# master.net
KiCad netlist of a schematic drawn in EAGLE
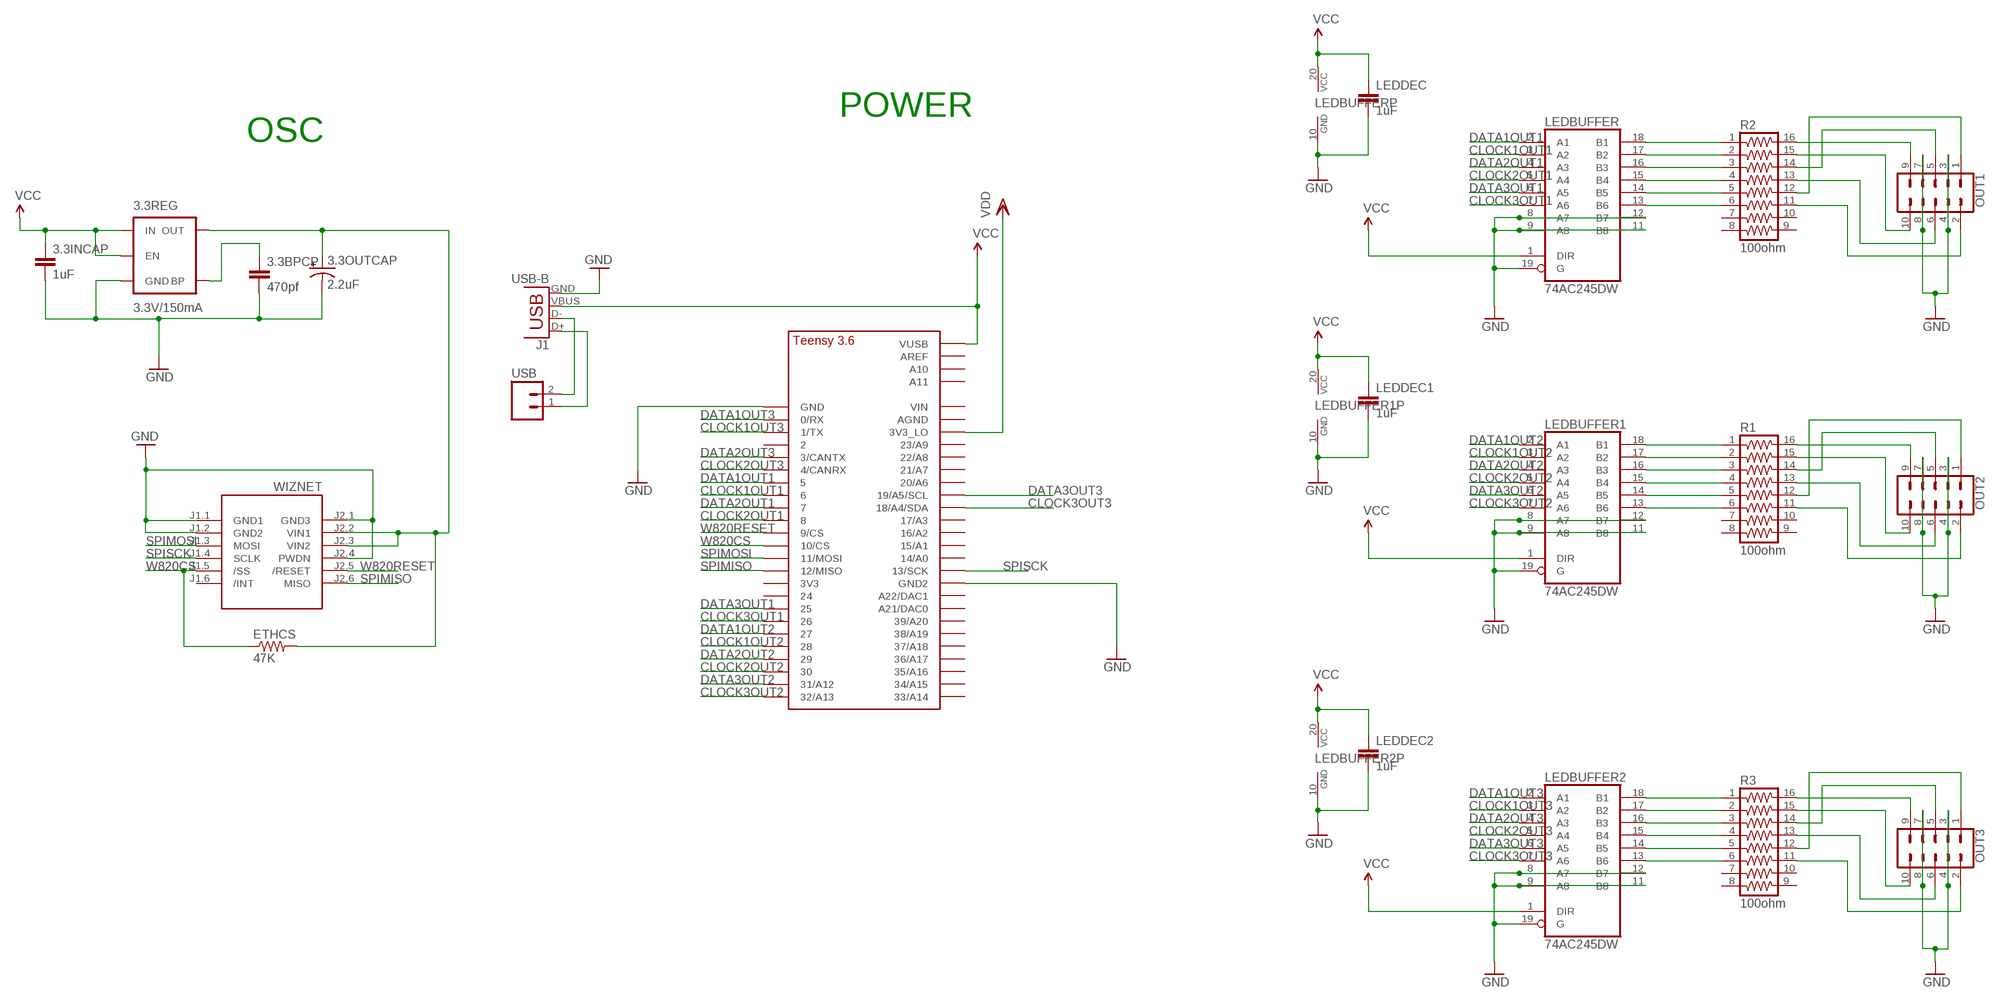
[diagram p0: schematic, sheet 1]

(export (version "E")
  (design (tool "Eeschema 10.0.6"))
  (components
    (comp (ref "3.3BPCP")
      (value "470pf")
      (footprint "eagle-import:1206")
      (libsource (lib "eagle-import") (part "CAP1206"))
    )
    (comp (ref "3.3INCAP")
      (value "1uF")
      (footprint "eagle-import:1206")
      (libsource (lib "eagle-import") (part "CAP1206"))
    )
    (comp (ref "3.3OUTCAP")
      (value "2.2uF")
      (footprint "eagle-import:EIA3528-KIT")
      (libsource (lib "eagle-import") (part "CAP_POL3528-KIT"))
    )
    (comp (ref "3.3REG")
      (value "3.3V/150mA")
      (footprint "eagle-import:SOT23-5")
      (libsource (lib "eagle-import") (part "V_REG_MIC52053.3V"))
    )
    (comp (ref "ETHCS")
      (value "47K")
      (footprint "eagle-import:1206")
      (libsource (lib "eagle-import") (part "RESISTOR1206"))
    )
    (comp (ref "J1")
      (value "USB-B")
      (footprint "eagle-import:USB-B-PTH")
      (libsource (lib "eagle-import") (part "USBPTH"))
    )
    (comp (ref "LEDBUFFER")
      (value "74AC245DW")
      (footprint "eagle-import:SO20W")
      (libsource (lib "eagle-import") (part "74245DWAC"))
    )
    (comp (ref "LEDBUFFER1")
      (value "74AC245DW")
      (footprint "eagle-import:SO20W")
      (libsource (lib "eagle-import") (part "74245DWAC"))
    )
    (comp (ref "LEDBUFFER2")
      (value "74AC245DW")
      (footprint "eagle-import:SO20W")
      (libsource (lib "eagle-import") (part "74245DWAC"))
    )
    (comp (ref "LEDDEC")
      (value "1uF")
      (footprint "eagle-import:1206")
      (libsource (lib "eagle-import") (part "CAP1206"))
    )
    (comp (ref "LEDDEC1")
      (value "1uF")
      (footprint "eagle-import:1206")
      (libsource (lib "eagle-import") (part "CAP1206"))
    )
    (comp (ref "LEDDEC2")
      (value "1uF")
      (footprint "eagle-import:1206")
      (libsource (lib "eagle-import") (part "CAP1206"))
    )
    (comp (ref "OUT1")
      (value "CONN_05X2SHD_LOCK")
      (footprint "eagle-import:2X5-SHROUDED_LOCK")
      (libsource (lib "eagle-import") (part "CONN_05X2SHD_LOCK"))
    )
    (comp (ref "OUT2")
      (value "CONN_05X2SHD_LOCK")
      (footprint "eagle-import:2X5-SHROUDED_LOCK")
      (libsource (lib "eagle-import") (part "CONN_05X2SHD_LOCK"))
    )
    (comp (ref "OUT3")
      (value "CONN_05X2SHD_LOCK")
      (footprint "eagle-import:2X5-SHROUDED_LOCK")
      (libsource (lib "eagle-import") (part "CONN_05X2SHD_LOCK"))
    )
    (comp (ref "R1")
      (value "100ohm")
      (footprint "eagle-import:SO16")
      (libsource (lib "eagle-import") (part "2NBS16-8"))
    )
    (comp (ref "R2")
      (value "100ohm")
      (footprint "eagle-import:SO16")
      (libsource (lib "eagle-import") (part "2NBS16-8"))
    )
    (comp (ref "R3")
      (value "100ohm")
      (footprint "eagle-import:SO16")
      (libsource (lib "eagle-import") (part "2NBS16-8"))
    )
    (comp (ref "U$1")
      (value "TEENSY_3.5/3.6_BASIC")
      (footprint "eagle-import:TEENSY_3.5_3.6_BASIC")
      (libsource (lib "eagle-import") (part "TEENSY_3.5/3.6_BASIC"))
    )
    (comp (ref "USB")
      (value "M02LOCK_LONGPADS")
      (footprint "eagle-import:1X02_LOCK_LONGPADS")
      (libsource (lib "eagle-import") (part "M02LOCK_LONGPADS"))
    )
    (comp (ref "WIZNET")
      (value "WIZ820IO_DEVICE'DUAL-IN-LINE'")
      (footprint "eagle-import:WIZ820IO")
      (libsource (lib "eagle-import") (part "WIZ820IO_DEVICE'DUAL-IN-LINE'"))
    )
  )
  (nets
    (net (code "1") (name "/CLOCK1OUT1") (class "Default")
      (node (ref "LEDBUFFER") (pin "3") (pinfunction "A2_3") (pintype "bidirectional"))
      (node (ref "U$1") (pin "6") (pinfunction "6_6") (pintype "bidirectional"))
    )
    (net (code "2") (name "/CLOCK1OUT2") (class "Default")
      (node (ref "LEDBUFFER1") (pin "3") (pinfunction "A2_3") (pintype "bidirectional"))
      (node (ref "U$1") (pin "28") (pinfunction "28_28") (pintype "bidirectional"))
    )
    (net (code "3") (name "/CLOCK1OUT3") (class "Default")
      (node (ref "LEDBUFFER2") (pin "3") (pinfunction "A2_3") (pintype "bidirectional"))
      (node (ref "U$1") (pin "1/TX") (pinfunction "1/TX_1/TX") (pintype "bidirectional"))
    )
    (net (code "4") (name "/CLOCK2OUT1") (class "Default")
      (node (ref "LEDBUFFER") (pin "5") (pinfunction "A4_5") (pintype "bidirectional"))
      (node (ref "U$1") (pin "8") (pinfunction "8_8") (pintype "bidirectional"))
    )
    (net (code "5") (name "/CLOCK2OUT2") (class "Default")
      (node (ref "LEDBUFFER1") (pin "5") (pinfunction "A4_5") (pintype "bidirectional"))
      (node (ref "U$1") (pin "30") (pinfunction "30_30") (pintype "bidirectional"))
    )
    (net (code "6") (name "/CLOCK2OUT3") (class "Default")
      (node (ref "LEDBUFFER2") (pin "5") (pinfunction "A4_5") (pintype "bidirectional"))
      (node (ref "U$1") (pin "4/CANRX") (pinfunction "4/CANRX_4/CANRX") (pintype "bidirectional"))
    )
    (net (code "7") (name "/CLOCK3OUT1") (class "Default")
      (node (ref "LEDBUFFER") (pin "7") (pinfunction "A6_7") (pintype "bidirectional"))
      (node (ref "U$1") (pin "26") (pinfunction "26_26") (pintype "bidirectional"))
    )
    (net (code "8") (name "/CLOCK3OUT2") (class "Default")
      (node (ref "LEDBUFFER1") (pin "7") (pinfunction "A6_7") (pintype "bidirectional"))
      (node (ref "U$1") (pin "32/A13") (pinfunction "32/A13_32/A13") (pintype "bidirectional"))
    )
    (net (code "9") (name "/CLOCK3OUT3") (class "Default")
      (node (ref "LEDBUFFER2") (pin "7") (pinfunction "A6_7") (pintype "bidirectional"))
      (node (ref "U$1") (pin "18/A4/SDA") (pinfunction "18/A4/SDA_18/A4/SDA") (pintype "bidirectional"))
    )
    (net (code "10") (name "/DATA1OUT1") (class "Default")
      (node (ref "LEDBUFFER") (pin "2") (pinfunction "A1_2") (pintype "bidirectional"))
      (node (ref "U$1") (pin "5") (pinfunction "5_5") (pintype "bidirectional"))
    )
    (net (code "11") (name "/DATA1OUT2") (class "Default")
      (node (ref "LEDBUFFER1") (pin "2") (pinfunction "A1_2") (pintype "bidirectional"))
      (node (ref "U$1") (pin "27") (pinfunction "27_27") (pintype "bidirectional"))
    )
    (net (code "12") (name "/DATA1OUT3") (class "Default")
      (node (ref "LEDBUFFER2") (pin "2") (pinfunction "A1_2") (pintype "bidirectional"))
      (node (ref "U$1") (pin "0/RX") (pinfunction "0/RX_0/RX") (pintype "bidirectional"))
    )
    (net (code "13") (name "/DATA2OUT1") (class "Default")
      (node (ref "LEDBUFFER") (pin "4") (pinfunction "A3_4") (pintype "bidirectional"))
      (node (ref "U$1") (pin "7") (pinfunction "7_7") (pintype "bidirectional"))
    )
    (net (code "14") (name "/DATA2OUT2") (class "Default")
      (node (ref "LEDBUFFER1") (pin "4") (pinfunction "A3_4") (pintype "bidirectional"))
      (node (ref "U$1") (pin "29") (pinfunction "29_29") (pintype "bidirectional"))
    )
    (net (code "15") (name "/DATA2OUT3") (class "Default")
      (node (ref "LEDBUFFER2") (pin "4") (pinfunction "A3_4") (pintype "bidirectional"))
      (node (ref "U$1") (pin "3/CANTX") (pinfunction "3/CANTX_3/CANTX") (pintype "bidirectional"))
    )
    (net (code "16") (name "/DATA3OUT1") (class "Default")
      (node (ref "LEDBUFFER") (pin "6") (pinfunction "A5_6") (pintype "bidirectional"))
      (node (ref "U$1") (pin "25") (pinfunction "25_25") (pintype "bidirectional"))
    )
    (net (code "17") (name "/DATA3OUT2") (class "Default")
      (node (ref "LEDBUFFER1") (pin "6") (pinfunction "A5_6") (pintype "bidirectional"))
      (node (ref "U$1") (pin "31/A12") (pinfunction "31/A12_31/A12") (pintype "bidirectional"))
    )
    (net (code "18") (name "/DATA3OUT3") (class "Default")
      (node (ref "LEDBUFFER2") (pin "6") (pinfunction "A5_6") (pintype "bidirectional"))
      (node (ref "U$1") (pin "19/A5/SCL") (pinfunction "19/A5/SCL_19/A5/SCL") (pintype "bidirectional"))
    )
    (net (code "19") (name "/SPIMISO") (class "Default")
      (node (ref "U$1") (pin "12/MISO") (pinfunction "12/MISO_12/MISO") (pintype "bidirectional"))
      (node (ref "WIZNET") (pin "J2.6") (pinfunction "MISO_J2.6") (pintype "output"))
    )
    (net (code "20") (name "/SPIMOSI") (class "Default")
      (node (ref "U$1") (pin "11/MOSI") (pinfunction "11/MOSI_11/MOSI") (pintype "bidirectional"))
      (node (ref "WIZNET") (pin "J1.3") (pinfunction "MOSI_J1.3") (pintype "input"))
    )
    (net (code "21") (name "/SPISCK") (class "Default")
      (node (ref "U$1") (pin "13/SCK") (pinfunction "13/SCK_13/SCK") (pintype "bidirectional"))
      (node (ref "WIZNET") (pin "J1.4") (pinfunction "SCLK_J1.4") (pintype "input"))
    )
    (net (code "22") (name "/W820CS") (class "Default")
      (node (ref "ETHCS") (pin "1") (pinfunction "1_1") (pintype "passive"))
      (node (ref "U$1") (pin "10/CS") (pinfunction "10/CS_10/CS") (pintype "bidirectional"))
      (node (ref "WIZNET") (pin "J1.5") (pinfunction "/SS_J1.5") (pintype "input"))
    )
    (net (code "23") (name "/W820RESET") (class "Default")
      (node (ref "U$1") (pin "9/CS") (pinfunction "9/CS_9/CS") (pintype "bidirectional"))
      (node (ref "WIZNET") (pin "J2.5") (pinfunction "/RESET_J2.5") (pintype "input"))
    )
    (net (code "24") (name "GND") (class "Default")
      (node (ref "3.3BPCP") (pin "2") (pinfunction "2_2") (pintype "passive"))
      (node (ref "3.3INCAP") (pin "2") (pinfunction "2_2") (pintype "passive"))
      (node (ref "3.3OUTCAP") (pin "C") (pinfunction "-_C") (pintype "passive"))
      (node (ref "3.3REG") (pin "2") (pinfunction "GND_2") (pintype "input"))
      (node (ref "J1") (pin "GND") (pinfunction "GND_GND") (pintype "bidirectional"))
      (node (ref "LEDBUFFER") (pin "10") (pinfunction "GND_10") (pintype "power_in"))
      (node (ref "LEDBUFFER") (pin "11") (pinfunction "B8_11") (pintype "bidirectional"))
      (node (ref "LEDBUFFER") (pin "12") (pinfunction "B7_12") (pintype "bidirectional"))
      (node (ref "LEDBUFFER") (pin "19") (pinfunction "G_19") (pintype "input"))
      (node (ref "LEDBUFFER") (pin "8") (pinfunction "A7_8") (pintype "bidirectional"))
      (node (ref "LEDBUFFER") (pin "9") (pinfunction "A8_9") (pintype "bidirectional"))
      (node (ref "LEDBUFFER1") (pin "10") (pinfunction "GND_10") (pintype "power_in"))
      (node (ref "LEDBUFFER1") (pin "11") (pinfunction "B8_11") (pintype "bidirectional"))
      (node (ref "LEDBUFFER1") (pin "12") (pinfunction "B7_12") (pintype "bidirectional"))
      (node (ref "LEDBUFFER1") (pin "19") (pinfunction "G_19") (pintype "input"))
      (node (ref "LEDBUFFER1") (pin "8") (pinfunction "A7_8") (pintype "bidirectional"))
      (node (ref "LEDBUFFER1") (pin "9") (pinfunction "A8_9") (pintype "bidirectional"))
      (node (ref "LEDBUFFER2") (pin "10") (pinfunction "GND_10") (pintype "power_in"))
      (node (ref "LEDBUFFER2") (pin "11") (pinfunction "B8_11") (pintype "bidirectional"))
      (node (ref "LEDBUFFER2") (pin "12") (pinfunction "B7_12") (pintype "bidirectional"))
      (node (ref "LEDBUFFER2") (pin "19") (pinfunction "G_19") (pintype "input"))
      (node (ref "LEDBUFFER2") (pin "8") (pinfunction "A7_8") (pintype "bidirectional"))
      (node (ref "LEDBUFFER2") (pin "9") (pinfunction "A8_9") (pintype "bidirectional"))
      (node (ref "LEDDEC") (pin "2") (pinfunction "2_2") (pintype "passive"))
      (node (ref "LEDDEC1") (pin "2") (pinfunction "2_2") (pintype "passive"))
      (node (ref "LEDDEC2") (pin "2") (pinfunction "2_2") (pintype "passive"))
      (node (ref "OUT1") (pin "3") (pinfunction "3_3") (pintype "passive"))
      (node (ref "OUT1") (pin "4") (pinfunction "4_4") (pintype "passive"))
      (node (ref "OUT1") (pin "7") (pinfunction "7_7") (pintype "passive"))
      (node (ref "OUT1") (pin "8") (pinfunction "8_8") (pintype "passive"))
      (node (ref "OUT2") (pin "3") (pinfunction "3_3") (pintype "passive"))
      (node (ref "OUT2") (pin "4") (pinfunction "4_4") (pintype "passive"))
      (node (ref "OUT2") (pin "7") (pinfunction "7_7") (pintype "passive"))
      (node (ref "OUT2") (pin "8") (pinfunction "8_8") (pintype "passive"))
      (node (ref "OUT3") (pin "3") (pinfunction "3_3") (pintype "passive"))
      (node (ref "OUT3") (pin "4") (pinfunction "4_4") (pintype "passive"))
      (node (ref "OUT3") (pin "7") (pinfunction "7_7") (pintype "passive"))
      (node (ref "OUT3") (pin "8") (pinfunction "8_8") (pintype "passive"))
      (node (ref "U$1") (pin "GND") (pinfunction "GND_GND") (pintype "bidirectional"))
      (node (ref "U$1") (pin "GND2") (pinfunction "GND2_GND2") (pintype "bidirectional"))
      (node (ref "WIZNET") (pin "J1.1") (pinfunction "GND1_J1.1") (pintype "power_in"))
      (node (ref "WIZNET") (pin "J1.2") (pinfunction "GND2_J1.2") (pintype "power_in"))
      (node (ref "WIZNET") (pin "J2.1") (pinfunction "GND3_J2.1") (pintype "power_in"))
      (node (ref "WIZNET") (pin "J2.4") (pinfunction "PWDN_J2.4") (pintype "input"))
    )
    (net (code "25") (name "Net-(3.3OUTCAP-+)") (class "Default")
      (node (ref "3.3OUTCAP") (pin "A") (pinfunction "+_A") (pintype "passive"))
      (node (ref "3.3REG") (pin "5") (pinfunction "OUT_5") (pintype "passive"))
      (node (ref "ETHCS") (pin "2") (pinfunction "2_2") (pintype "passive"))
      (node (ref "WIZNET") (pin "J2.2") (pinfunction "VIN1_J2.2") (pintype "power_in"))
      (node (ref "WIZNET") (pin "J2.3") (pinfunction "VIN2_J2.3") (pintype "power_in"))
    )
    (net (code "26") (name "Net-(3.3REG-BP)") (class "Default")
      (node (ref "3.3BPCP") (pin "1") (pinfunction "1_1") (pintype "passive"))
      (node (ref "3.3REG") (pin "4") (pinfunction "BP_4") (pintype "input"))
    )
    (net (code "27") (name "Net-(J1-PadD+)") (class "Default")
      (node (ref "J1") (pin "D+") (pinfunction "D+_D+") (pintype "bidirectional"))
      (node (ref "USB") (pin "1") (pinfunction "1_1") (pintype "passive"))
    )
    (net (code "28") (name "Net-(J1-PadD-)") (class "Default")
      (node (ref "J1") (pin "D-") (pinfunction "D-_D-") (pintype "bidirectional"))
      (node (ref "USB") (pin "2") (pinfunction "2_2") (pintype "passive"))
    )
    (net (code "29") (name "Net-(LEDBUFFER1A-B1)") (class "Default")
      (node (ref "LEDBUFFER1") (pin "18") (pinfunction "B1_18") (pintype "bidirectional"))
      (node (ref "R1") (pin "1") (pinfunction "1_1") (pintype "passive"))
    )
    (net (code "30") (name "Net-(LEDBUFFER1A-B2)") (class "Default")
      (node (ref "LEDBUFFER1") (pin "17") (pinfunction "B2_17") (pintype "bidirectional"))
      (node (ref "R1") (pin "2") (pinfunction "2_2") (pintype "passive"))
    )
    (net (code "31") (name "Net-(LEDBUFFER1A-B3)") (class "Default")
      (node (ref "LEDBUFFER1") (pin "16") (pinfunction "B3_16") (pintype "bidirectional"))
      (node (ref "R1") (pin "3") (pinfunction "3_3") (pintype "passive"))
    )
    (net (code "32") (name "Net-(LEDBUFFER1A-B4)") (class "Default")
      (node (ref "LEDBUFFER1") (pin "15") (pinfunction "B4_15") (pintype "bidirectional"))
      (node (ref "R1") (pin "4") (pinfunction "4_4") (pintype "passive"))
    )
    (net (code "33") (name "Net-(LEDBUFFER1A-B5)") (class "Default")
      (node (ref "LEDBUFFER1") (pin "14") (pinfunction "B5_14") (pintype "bidirectional"))
      (node (ref "R1") (pin "5") (pinfunction "5_5") (pintype "passive"))
    )
    (net (code "34") (name "Net-(LEDBUFFER1A-B6)") (class "Default")
      (node (ref "LEDBUFFER1") (pin "13") (pinfunction "B6_13") (pintype "bidirectional"))
      (node (ref "R1") (pin "6") (pinfunction "6_6") (pintype "passive"))
    )
    (net (code "35") (name "Net-(LEDBUFFER2A-B1)") (class "Default")
      (node (ref "LEDBUFFER2") (pin "18") (pinfunction "B1_18") (pintype "bidirectional"))
      (node (ref "R3") (pin "1") (pinfunction "1_1") (pintype "passive"))
    )
    (net (code "36") (name "Net-(LEDBUFFER2A-B2)") (class "Default")
      (node (ref "LEDBUFFER2") (pin "17") (pinfunction "B2_17") (pintype "bidirectional"))
      (node (ref "R3") (pin "2") (pinfunction "2_2") (pintype "passive"))
    )
    (net (code "37") (name "Net-(LEDBUFFER2A-B3)") (class "Default")
      (node (ref "LEDBUFFER2") (pin "16") (pinfunction "B3_16") (pintype "bidirectional"))
      (node (ref "R3") (pin "3") (pinfunction "3_3") (pintype "passive"))
    )
    (net (code "38") (name "Net-(LEDBUFFER2A-B4)") (class "Default")
      (node (ref "LEDBUFFER2") (pin "15") (pinfunction "B4_15") (pintype "bidirectional"))
      (node (ref "R3") (pin "4") (pinfunction "4_4") (pintype "passive"))
    )
    (net (code "39") (name "Net-(LEDBUFFER2A-B5)") (class "Default")
      (node (ref "LEDBUFFER2") (pin "14") (pinfunction "B5_14") (pintype "bidirectional"))
      (node (ref "R3") (pin "5") (pinfunction "5_5") (pintype "passive"))
    )
    (net (code "40") (name "Net-(LEDBUFFER2A-B6)") (class "Default")
      (node (ref "LEDBUFFER2") (pin "13") (pinfunction "B6_13") (pintype "bidirectional"))
      (node (ref "R3") (pin "6") (pinfunction "6_6") (pintype "passive"))
    )
    (net (code "41") (name "Net-(LEDBUFFERA-B1)") (class "Default")
      (node (ref "LEDBUFFER") (pin "18") (pinfunction "B1_18") (pintype "bidirectional"))
      (node (ref "R2") (pin "1") (pinfunction "1_1") (pintype "passive"))
    )
    (net (code "42") (name "Net-(LEDBUFFERA-B2)") (class "Default")
      (node (ref "LEDBUFFER") (pin "17") (pinfunction "B2_17") (pintype "bidirectional"))
      (node (ref "R2") (pin "2") (pinfunction "2_2") (pintype "passive"))
    )
    (net (code "43") (name "Net-(LEDBUFFERA-B3)") (class "Default")
      (node (ref "LEDBUFFER") (pin "16") (pinfunction "B3_16") (pintype "bidirectional"))
      (node (ref "R2") (pin "3") (pinfunction "3_3") (pintype "passive"))
    )
    (net (code "44") (name "Net-(LEDBUFFERA-B4)") (class "Default")
      (node (ref "LEDBUFFER") (pin "15") (pinfunction "B4_15") (pintype "bidirectional"))
      (node (ref "R2") (pin "4") (pinfunction "4_4") (pintype "passive"))
    )
    (net (code "45") (name "Net-(LEDBUFFERA-B5)") (class "Default")
      (node (ref "LEDBUFFER") (pin "14") (pinfunction "B5_14") (pintype "bidirectional"))
      (node (ref "R2") (pin "5") (pinfunction "5_5") (pintype "passive"))
    )
    (net (code "46") (name "Net-(LEDBUFFERA-B6)") (class "Default")
      (node (ref "LEDBUFFER") (pin "13") (pinfunction "B6_13") (pintype "bidirectional"))
      (node (ref "R2") (pin "6") (pinfunction "6_6") (pintype "passive"))
    )
    (net (code "47") (name "Net-(OUT1-Pad1)") (class "Default")
      (node (ref "OUT1") (pin "1") (pinfunction "1_1") (pintype "passive"))
      (node (ref "R2") (pin "12") (pinfunction "12_12") (pintype "passive"))
    )
    (net (code "48") (name "Net-(OUT1-Pad2)") (class "Default")
      (node (ref "OUT1") (pin "2") (pinfunction "2_2") (pintype "passive"))
      (node (ref "R2") (pin "11") (pinfunction "11_11") (pintype "passive"))
    )
    (net (code "49") (name "Net-(OUT1-Pad5)") (class "Default")
      (node (ref "OUT1") (pin "5") (pinfunction "5_5") (pintype "passive"))
      (node (ref "R2") (pin "14") (pinfunction "14_14") (pintype "passive"))
    )
    (net (code "50") (name "Net-(OUT1-Pad6)") (class "Default")
      (node (ref "OUT1") (pin "6") (pinfunction "6_6") (pintype "passive"))
      (node (ref "R2") (pin "13") (pinfunction "13_13") (pintype "passive"))
    )
    (net (code "51") (name "Net-(OUT1-Pad9)") (class "Default")
      (node (ref "OUT1") (pin "9") (pinfunction "9_9") (pintype "passive"))
      (node (ref "R2") (pin "16") (pinfunction "16_16") (pintype "passive"))
    )
    (net (code "52") (name "Net-(OUT1-Pad10)") (class "Default")
      (node (ref "OUT1") (pin "10") (pinfunction "10_10") (pintype "passive"))
      (node (ref "R2") (pin "15") (pinfunction "15_15") (pintype "passive"))
    )
    (net (code "53") (name "Net-(OUT2-Pad1)") (class "Default")
      (node (ref "OUT2") (pin "1") (pinfunction "1_1") (pintype "passive"))
      (node (ref "R1") (pin "12") (pinfunction "12_12") (pintype "passive"))
    )
    (net (code "54") (name "Net-(OUT2-Pad2)") (class "Default")
      (node (ref "OUT2") (pin "2") (pinfunction "2_2") (pintype "passive"))
      (node (ref "R1") (pin "11") (pinfunction "11_11") (pintype "passive"))
    )
    (net (code "55") (name "Net-(OUT2-Pad5)") (class "Default")
      (node (ref "OUT2") (pin "5") (pinfunction "5_5") (pintype "passive"))
      (node (ref "R1") (pin "14") (pinfunction "14_14") (pintype "passive"))
    )
    (net (code "56") (name "Net-(OUT2-Pad6)") (class "Default")
      (node (ref "OUT2") (pin "6") (pinfunction "6_6") (pintype "passive"))
      (node (ref "R1") (pin "13") (pinfunction "13_13") (pintype "passive"))
    )
    (net (code "57") (name "Net-(OUT2-Pad9)") (class "Default")
      (node (ref "OUT2") (pin "9") (pinfunction "9_9") (pintype "passive"))
      (node (ref "R1") (pin "16") (pinfunction "16_16") (pintype "passive"))
    )
    (net (code "58") (name "Net-(OUT2-Pad10)") (class "Default")
      (node (ref "OUT2") (pin "10") (pinfunction "10_10") (pintype "passive"))
      (node (ref "R1") (pin "15") (pinfunction "15_15") (pintype "passive"))
    )
    (net (code "59") (name "Net-(OUT3-Pad1)") (class "Default")
      (node (ref "OUT3") (pin "1") (pinfunction "1_1") (pintype "passive"))
      (node (ref "R3") (pin "12") (pinfunction "12_12") (pintype "passive"))
    )
    (net (code "60") (name "Net-(OUT3-Pad2)") (class "Default")
      (node (ref "OUT3") (pin "2") (pinfunction "2_2") (pintype "passive"))
      (node (ref "R3") (pin "11") (pinfunction "11_11") (pintype "passive"))
    )
    (net (code "61") (name "Net-(OUT3-Pad5)") (class "Default")
      (node (ref "OUT3") (pin "5") (pinfunction "5_5") (pintype "passive"))
      (node (ref "R3") (pin "14") (pinfunction "14_14") (pintype "passive"))
    )
    (net (code "62") (name "Net-(OUT3-Pad6)") (class "Default")
      (node (ref "OUT3") (pin "6") (pinfunction "6_6") (pintype "passive"))
      (node (ref "R3") (pin "13") (pinfunction "13_13") (pintype "passive"))
    )
    (net (code "63") (name "Net-(OUT3-Pad9)") (class "Default")
      (node (ref "OUT3") (pin "9") (pinfunction "9_9") (pintype "passive"))
      (node (ref "R3") (pin "16") (pinfunction "16_16") (pintype "passive"))
    )
    (net (code "64") (name "Net-(OUT3-Pad10)") (class "Default")
      (node (ref "OUT3") (pin "10") (pinfunction "10_10") (pintype "passive"))
      (node (ref "R3") (pin "15") (pinfunction "15_15") (pintype "passive"))
    )
    (net (code "65") (name "VCC") (class "Default")
      (node (ref "3.3INCAP") (pin "1") (pinfunction "1_1") (pintype "passive"))
      (node (ref "3.3REG") (pin "1") (pinfunction "IN_1") (pintype "input"))
      (node (ref "3.3REG") (pin "3") (pinfunction "EN_3") (pintype "input"))
      (node (ref "J1") (pin "VBUS") (pinfunction "VBUS_VBUS") (pintype "bidirectional"))
      (node (ref "LEDBUFFER") (pin "1") (pinfunction "DIR_1") (pintype "input"))
      (node (ref "LEDBUFFER") (pin "20") (pinfunction "VCC_20") (pintype "power_in"))
      (node (ref "LEDBUFFER1") (pin "1") (pinfunction "DIR_1") (pintype "input"))
      (node (ref "LEDBUFFER1") (pin "20") (pinfunction "VCC_20") (pintype "power_in"))
      (node (ref "LEDBUFFER2") (pin "1") (pinfunction "DIR_1") (pintype "input"))
      (node (ref "LEDBUFFER2") (pin "20") (pinfunction "VCC_20") (pintype "power_in"))
      (node (ref "LEDDEC") (pin "1") (pinfunction "1_1") (pintype "passive"))
      (node (ref "LEDDEC1") (pin "1") (pinfunction "1_1") (pintype "passive"))
      (node (ref "LEDDEC2") (pin "1") (pinfunction "1_1") (pintype "passive"))
      (node (ref "U$1") (pin "VUSB") (pinfunction "VUSB_VUSB") (pintype "bidirectional"))
    )
    (net (code "66") (name "VDD") (class "Default")
      (node (ref "U$1") (pin "3V3_LO") (pinfunction "3V3_LO_3V3_LO") (pintype "bidirectional"))
    )
    (net (code "67") (name "unconnected-(R1-Pad7)") (class "Default")
      (node (ref "R1") (pin "7") (pinfunction "7_7") (pintype "passive"))
    )
    (net (code "68") (name "unconnected-(R1-Pad8)") (class "Default")
      (node (ref "R1") (pin "8") (pinfunction "8_8") (pintype "passive"))
    )
    (net (code "69") (name "unconnected-(R1-Pad9)") (class "Default")
      (node (ref "R1") (pin "9") (pinfunction "9_9") (pintype "passive"))
    )
    (net (code "70") (name "unconnected-(R1-Pad10)") (class "Default")
      (node (ref "R1") (pin "10") (pinfunction "10_10") (pintype "passive"))
    )
    (net (code "71") (name "unconnected-(R2-Pad7)") (class "Default")
      (node (ref "R2") (pin "7") (pinfunction "7_7") (pintype "passive"))
    )
    (net (code "72") (name "unconnected-(R2-Pad8)") (class "Default")
      (node (ref "R2") (pin "8") (pinfunction "8_8") (pintype "passive"))
    )
    (net (code "73") (name "unconnected-(R2-Pad9)") (class "Default")
      (node (ref "R2") (pin "9") (pinfunction "9_9") (pintype "passive"))
    )
    (net (code "74") (name "unconnected-(R2-Pad10)") (class "Default")
      (node (ref "R2") (pin "10") (pinfunction "10_10") (pintype "passive"))
    )
    (net (code "75") (name "unconnected-(R3-Pad7)") (class "Default")
      (node (ref "R3") (pin "7") (pinfunction "7_7") (pintype "passive"))
    )
    (net (code "76") (name "unconnected-(R3-Pad8)") (class "Default")
      (node (ref "R3") (pin "8") (pinfunction "8_8") (pintype "passive"))
    )
    (net (code "77") (name "unconnected-(R3-Pad9)") (class "Default")
      (node (ref "R3") (pin "9") (pinfunction "9_9") (pintype "passive"))
    )
    (net (code "78") (name "unconnected-(R3-Pad10)") (class "Default")
      (node (ref "R3") (pin "10") (pinfunction "10_10") (pintype "passive"))
    )
    (net (code "79") (name "unconnected-(U$1-A21{slash}DAC0-Pad21{slash}DAC0)") (class "Default")
      (node (ref "U$1") (pin "21/DAC0") (pinfunction "A21/DAC0_21/DAC0") (pintype "bidirectional"))
    )
    (net (code "80") (name "unconnected-(U$1-Pad2)") (class "Default")
      (node (ref "U$1") (pin "2") (pinfunction "2_2") (pintype "bidirectional"))
    )
    (net (code "81") (name "unconnected-(U$1-Pad3V3)") (class "Default")
      (node (ref "U$1") (pin "3V3") (pinfunction "3V3_3V3") (pintype "bidirectional"))
    )
    (net (code "82") (name "unconnected-(U$1-Pad14{slash}A0)") (class "Default")
      (node (ref "U$1") (pin "14/A0") (pinfunction "14/A0_14/A0") (pintype "bidirectional"))
    )
    (net (code "83") (name "unconnected-(U$1-Pad15{slash}A1)") (class "Default")
      (node (ref "U$1") (pin "15/A1") (pinfunction "15/A1_15/A1") (pintype "bidirectional"))
    )
    (net (code "84") (name "unconnected-(U$1-Pad16{slash}A2)") (class "Default")
      (node (ref "U$1") (pin "16/A2") (pinfunction "16/A2_16/A2") (pintype "bidirectional"))
    )
    (net (code "85") (name "unconnected-(U$1-Pad17{slash}A3)") (class "Default")
      (node (ref "U$1") (pin "17/A3") (pinfunction "17/A3_17/A3") (pintype "bidirectional"))
    )
    (net (code "86") (name "unconnected-(U$1-Pad20{slash}A6)") (class "Default")
      (node (ref "U$1") (pin "20/A6") (pinfunction "20/A6_20/A6") (pintype "bidirectional"))
    )
    (net (code "87") (name "unconnected-(U$1-Pad21{slash}A7)") (class "Default")
      (node (ref "U$1") (pin "21/A7") (pinfunction "21/A7_21/A7") (pintype "bidirectional"))
    )
    (net (code "88") (name "unconnected-(U$1-Pad22{slash}A8)") (class "Default")
      (node (ref "U$1") (pin "22/A8") (pinfunction "22/A8_22/A8") (pintype "bidirectional"))
    )
    (net (code "89") (name "unconnected-(U$1-Pad23{slash}A9)") (class "Default")
      (node (ref "U$1") (pin "23/A9") (pinfunction "23/A9_23/A9") (pintype "bidirectional"))
    )
    (net (code "90") (name "unconnected-(U$1-Pad24)") (class "Default")
      (node (ref "U$1") (pin "24") (pinfunction "24_24") (pintype "bidirectional"))
    )
    (net (code "91") (name "unconnected-(U$1-Pad33{slash}A14)") (class "Default")
      (node (ref "U$1") (pin "33/A14") (pinfunction "33/A14_33/A14") (pintype "bidirectional"))
    )
    (net (code "92") (name "unconnected-(U$1-Pad34{slash}A15)") (class "Default")
      (node (ref "U$1") (pin "34/A15") (pinfunction "34/A15_34/A15") (pintype "bidirectional"))
    )
    (net (code "93") (name "unconnected-(U$1-Pad35{slash}A16)") (class "Default")
      (node (ref "U$1") (pin "35/A16") (pinfunction "35/A16_35/A16") (pintype "bidirectional"))
    )
    (net (code "94") (name "unconnected-(U$1-Pad36{slash}A17)") (class "Default")
      (node (ref "U$1") (pin "36/A17") (pinfunction "36/A17_36/A17") (pintype "bidirectional"))
    )
    (net (code "95") (name "unconnected-(U$1-Pad37{slash}A18)") (class "Default")
      (node (ref "U$1") (pin "37/A18") (pinfunction "37/A18_37/A18") (pintype "bidirectional"))
    )
    (net (code "96") (name "unconnected-(U$1-Pad38{slash}A19)") (class "Default")
      (node (ref "U$1") (pin "38/A19") (pinfunction "38/A19_38/A19") (pintype "bidirectional"))
    )
    (net (code "97") (name "unconnected-(U$1-Pad39{slash}A20)") (class "Default")
      (node (ref "U$1") (pin "39/A20") (pinfunction "39/A20_39/A20") (pintype "bidirectional"))
    )
    (net (code "98") (name "unconnected-(U$1-PadA10)") (class "Default")
      (node (ref "U$1") (pin "A10") (pinfunction "A10_A10") (pintype "bidirectional"))
    )
    (net (code "99") (name "unconnected-(U$1-PadA11)") (class "Default")
      (node (ref "U$1") (pin "A11") (pinfunction "A11_A11") (pintype "bidirectional"))
    )
    (net (code "100") (name "unconnected-(U$1-PadA22{slash}DAC1)") (class "Default")
      (node (ref "U$1") (pin "A22/DAC1") (pinfunction "A22/DAC1_A22/DAC1") (pintype "bidirectional"))
    )
    (net (code "101") (name "unconnected-(U$1-PadAGND)") (class "Default")
      (node (ref "U$1") (pin "AGND") (pinfunction "AGND_AGND") (pintype "bidirectional"))
    )
    (net (code "102") (name "unconnected-(U$1-PadAREF)") (class "Default")
      (node (ref "U$1") (pin "AREF") (pinfunction "AREF_AREF") (pintype "bidirectional"))
    )
    (net (code "103") (name "unconnected-(U$1-PadVIN)") (class "Default")
      (node (ref "U$1") (pin "VIN") (pinfunction "VIN_VIN") (pintype "bidirectional"))
    )
    (net (code "104") (name "unconnected-(WIZNET-{slash}INT-PadJ1.6)") (class "Default")
      (node (ref "WIZNET") (pin "J1.6") (pinfunction "/INT_J1.6") (pintype "output"))
    )
  )
)
